# Buck_60W20V_MCU_AuxPSU.net
KiCad netlist of a schematic drawn in Altium Designer
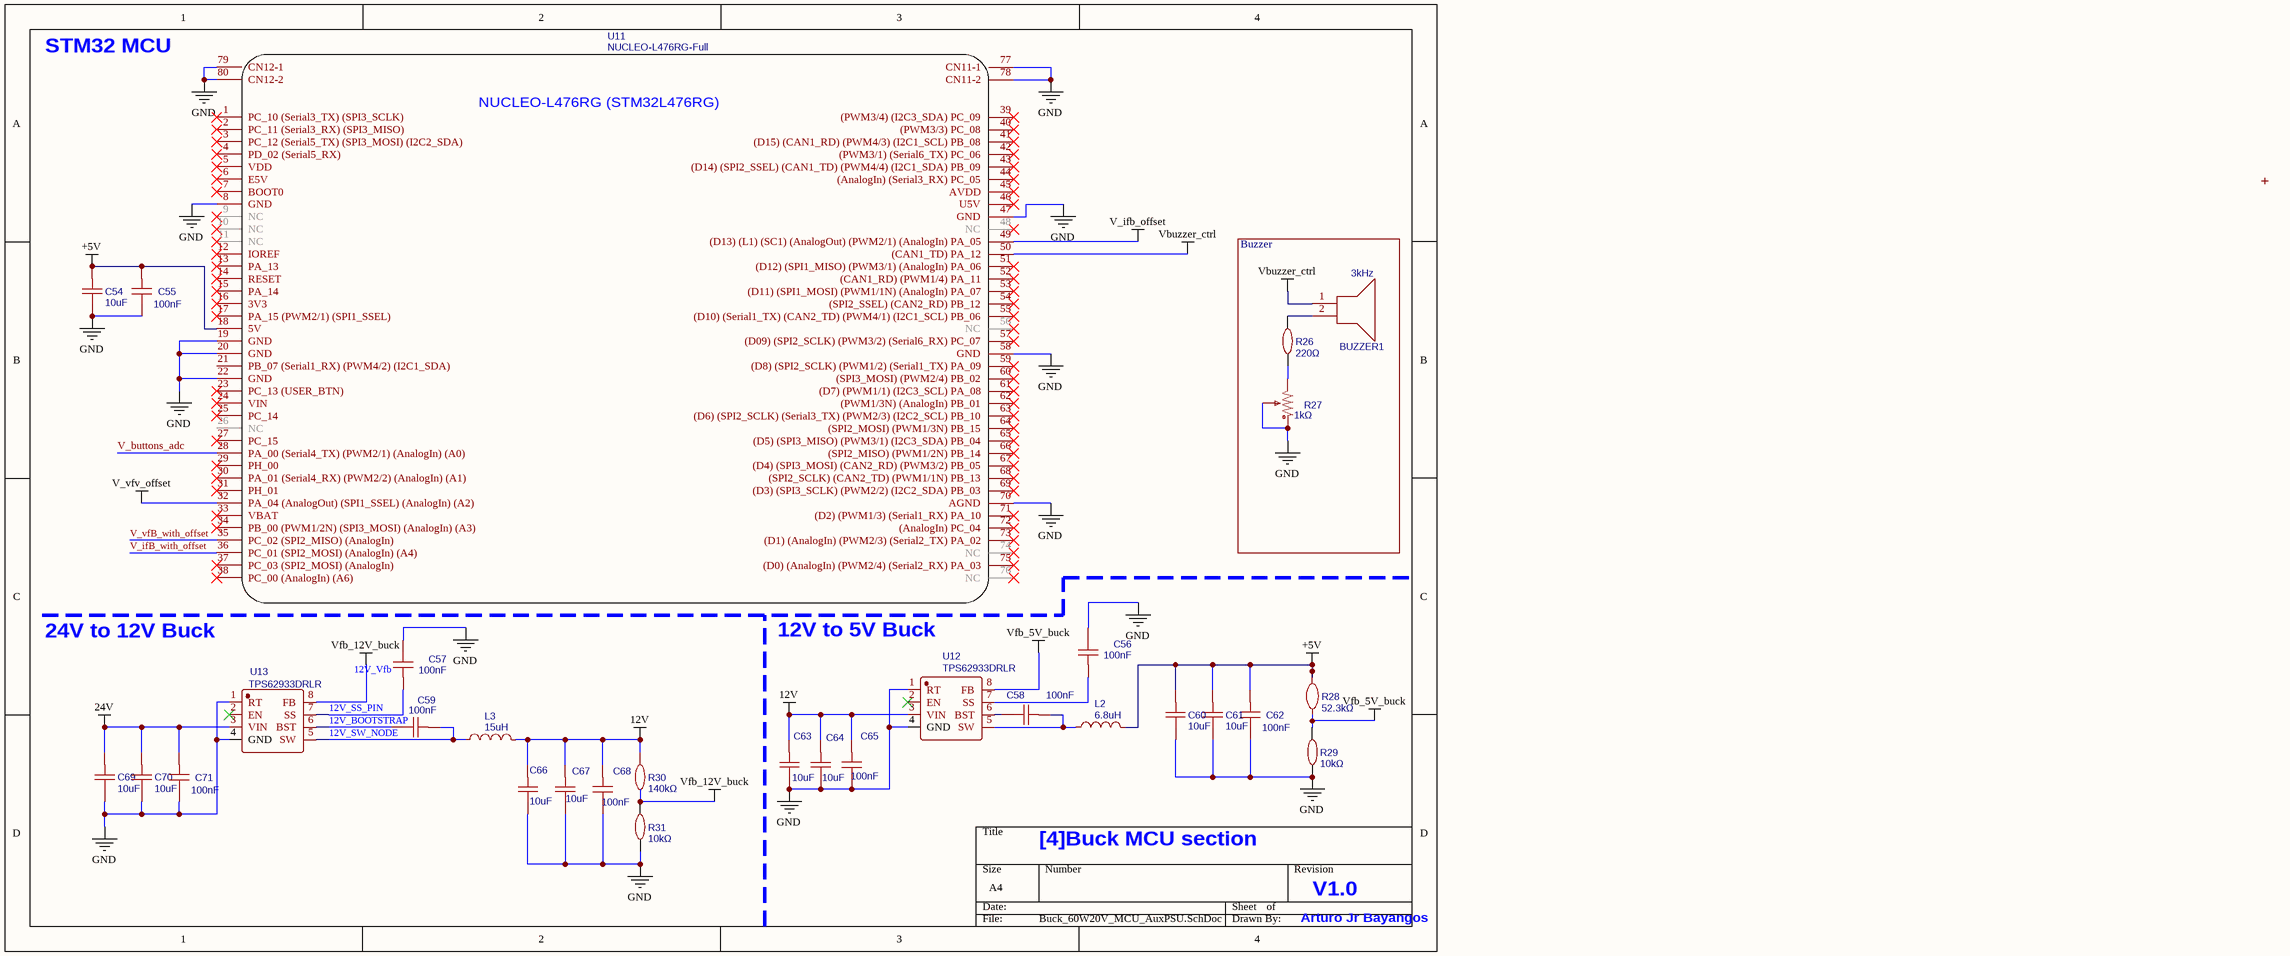
[diagram p0: Buck_60W20V_MCU_AuxPSU.SchDoc]

(export (version "E")
  (design (tool "Eeschema 10.0.6"))
  (components
    (comp (ref "BUZZER1")
      (value "3kHz")
      (footprint "BUZ-TH_BD9.0-P5.00-D0.6-FD")
      (fields
        (field (name "MANUFACTURER") "华能")
        (field (name "MANUFACTURER PART") "HNB09A03")
        (field (name "CONTRIBUTOR") "LCSC")
      )
      (libsource (lib "altium-import") (part "root_0_3kHz_"))
    )
    (comp (ref "C54")
      (value "10uF")
      (footprint "C1210")
      (fields
        (field (name "MANUFACTURER") "TAIYO YUDEN(太诱)")
        (field (name "MANUFACTURER PART") "UMK325AB7106KM-T")
        (field (name "CONTRIBUTOR") "LCSC")
      )
      (libsource (lib "altium-import") (part "root_1_10uF_"))
    )
    (comp (ref "C55")
      (value "100nF")
      (footprint "C0402")
      (fields
        (field (name "MANUFACTURER") "TAIYO YUDEN(太诱)")
        (field (name "MANUFACTURER PART") "UMK105B7104KV-FR")
        (field (name "CONTRIBUTOR") "lcsc")
      )
      (libsource (lib "altium-import") (part "root_1_100nF_"))
    )
    (comp (ref "C56")
      (value "100nF")
      (footprint "C0402")
      (fields
        (field (name "MANUFACTURER") "TAIYO YUDEN(太诱)")
        (field (name "MANUFACTURER PART") "UMK105B7104KV-FR")
        (field (name "CONTRIBUTOR") "lcsc")
      )
      (libsource (lib "altium-import") (part "root_3_100nF_"))
    )
    (comp (ref "C57")
      (value "100nF")
      (footprint "C0402")
      (fields
        (field (name "MANUFACTURER") "TAIYO YUDEN(太诱)")
        (field (name "MANUFACTURER PART") "UMK105B7104KV-FR")
        (field (name "CONTRIBUTOR") "lcsc")
      )
      (libsource (lib "altium-import") (part "root_3_100nF_"))
    )
    (comp (ref "C58")
      (value "100nF")
      (footprint "C0402")
      (fields
        (field (name "MANUFACTURER") "TAIYO YUDEN(太诱)")
        (field (name "MANUFACTURER PART") "UMK105B7104KV-FR")
        (field (name "CONTRIBUTOR") "lcsc")
      )
      (libsource (lib "altium-import") (part "root_0_100nF_"))
    )
    (comp (ref "C59")
      (value "100nF")
      (footprint "C0402")
      (fields
        (field (name "MANUFACTURER") "TAIYO YUDEN(太诱)")
        (field (name "MANUFACTURER PART") "UMK105B7104KV-FR")
        (field (name "CONTRIBUTOR") "lcsc")
      )
      (libsource (lib "altium-import") (part "root_0_100nF_"))
    )
    (comp (ref "C60")
      (value "10uF")
      (footprint "C1210")
      (fields
        (field (name "MANUFACTURER") "TAIYO YUDEN(太诱)")
        (field (name "MANUFACTURER PART") "UMK325AB7106KM-T")
        (field (name "CONTRIBUTOR") "LCSC")
      )
      (libsource (lib "altium-import") (part "root_1_10uF_"))
    )
    (comp (ref "C61")
      (value "10uF")
      (footprint "C1210")
      (fields
        (field (name "MANUFACTURER") "TAIYO YUDEN(太诱)")
        (field (name "MANUFACTURER PART") "UMK325AB7106KM-T")
        (field (name "CONTRIBUTOR") "LCSC")
      )
      (libsource (lib "altium-import") (part "root_1_10uF_"))
    )
    (comp (ref "C62")
      (value "100nF")
      (footprint "C0402")
      (fields
        (field (name "MANUFACTURER") "TAIYO YUDEN(太诱)")
        (field (name "MANUFACTURER PART") "UMK105B7104KV-FR")
        (field (name "CONTRIBUTOR") "lcsc")
      )
      (libsource (lib "altium-import") (part "root_1_100nF_"))
    )
    (comp (ref "C63")
      (value "10uF")
      (footprint "C1210")
      (fields
        (field (name "MANUFACTURER") "TAIYO YUDEN(太诱)")
        (field (name "MANUFACTURER PART") "UMK325AB7106KM-T")
        (field (name "CONTRIBUTOR") "LCSC")
      )
      (libsource (lib "altium-import") (part "root_1_10uF_"))
    )
    (comp (ref "C64")
      (value "10uF")
      (footprint "C1210")
      (fields
        (field (name "MANUFACTURER") "TAIYO YUDEN(太诱)")
        (field (name "MANUFACTURER PART") "UMK325AB7106KM-T")
        (field (name "CONTRIBUTOR") "LCSC")
      )
      (libsource (lib "altium-import") (part "root_1_10uF_"))
    )
    (comp (ref "C65")
      (value "100nF")
      (footprint "C0402")
      (fields
        (field (name "MANUFACTURER") "TAIYO YUDEN(太诱)")
        (field (name "MANUFACTURER PART") "UMK105B7104KV-FR")
        (field (name "CONTRIBUTOR") "lcsc")
      )
      (libsource (lib "altium-import") (part "root_1_100nF_"))
    )
    (comp (ref "C66")
      (value "10uF")
      (footprint "C1210")
      (fields
        (field (name "MANUFACTURER") "TAIYO YUDEN(太诱)")
        (field (name "MANUFACTURER PART") "UMK325AB7106KM-T")
        (field (name "CONTRIBUTOR") "LCSC")
      )
      (libsource (lib "altium-import") (part "root_1_10uF_"))
    )
    (comp (ref "C67")
      (value "10uF")
      (footprint "C1210")
      (fields
        (field (name "MANUFACTURER") "TAIYO YUDEN(太诱)")
        (field (name "MANUFACTURER PART") "UMK325AB7106KM-T")
        (field (name "CONTRIBUTOR") "LCSC")
      )
      (libsource (lib "altium-import") (part "root_1_10uF_"))
    )
    (comp (ref "C68")
      (value "100nF")
      (footprint "C0402")
      (fields
        (field (name "MANUFACTURER") "TAIYO YUDEN(太诱)")
        (field (name "MANUFACTURER PART") "UMK105B7104KV-FR")
        (field (name "CONTRIBUTOR") "lcsc")
      )
      (libsource (lib "altium-import") (part "root_1_100nF_"))
    )
    (comp (ref "C69")
      (value "10uF")
      (footprint "C1210")
      (fields
        (field (name "MANUFACTURER") "TAIYO YUDEN(太诱)")
        (field (name "MANUFACTURER PART") "UMK325AB7106KM-T")
        (field (name "CONTRIBUTOR") "LCSC")
      )
      (libsource (lib "altium-import") (part "root_1_10uF_"))
    )
    (comp (ref "C70")
      (value "10uF")
      (footprint "C1210")
      (fields
        (field (name "MANUFACTURER") "TAIYO YUDEN(太诱)")
        (field (name "MANUFACTURER PART") "UMK325AB7106KM-T")
        (field (name "CONTRIBUTOR") "LCSC")
      )
      (libsource (lib "altium-import") (part "root_1_10uF_"))
    )
    (comp (ref "C71")
      (value "100nF")
      (footprint "C0402")
      (fields
        (field (name "MANUFACTURER") "TAIYO YUDEN(太诱)")
        (field (name "MANUFACTURER PART") "UMK105B7104KV-FR")
        (field (name "CONTRIBUTOR") "lcsc")
      )
      (libsource (lib "altium-import") (part "root_1_100nF_"))
    )
    (comp (ref "L2")
      (value "6.8uH")
      (footprint "IND-SMD_L3.0-W3.0_LQH3NPN")
      (fields
        (field (name "MANUFACTURER") "muRata(村田)")
        (field (name "MANUFACTURER PART") "LQH3NPN6R8MMEL")
        (field (name "CONTRIBUTOR") "lcsc")
      )
      (libsource (lib "altium-import") (part "root_0_6.8uH_"))
    )
    (comp (ref "L3")
      (value "15uH")
      (footprint "IND-SMD_L7.2-W6.9")
      (fields
        (field (name "MANUFACTURER") "TDK")
        (field (name "MANUFACTURER PART") "SPM6545VT-150M-D")
        (field (name "CONTRIBUTOR") "lcsc")
      )
      (libsource (lib "altium-import") (part "root_0_15uH_"))
    )
    (comp (ref "R26")
      (value "220Ω")
      (footprint "R0603")
      (fields (field (name "MANUFACTURER") "RALEC(旺诠)") (field (name "MANUFACTURER PART") "RTT03221JTP"))
      (libsource (lib "altium-import") (part "root_1_220Ω_"))
    )
    (comp (ref "R27")
      (value "1kΩ")
      (footprint "RES-ADJ-TH_3296W")
      (fields
        (field (name "MANUFACTURER") "BOCHEN(博晨)")
        (field (name "MANUFACTURER PART") "3296W-1-102-8mm")
        (field (name "CONTRIBUTOR") "LCSC")
      )
      (libsource (lib "altium-import") (part "root_3_1kΩ_"))
    )
    (comp (ref "R28")
      (value "52.3kΩ")
      (footprint "R0603")
      (fields
        (field (name "MANUFACTURER") "PANASONIC(松下)")
        (field (name "MANUFACTURER PART") "ERA3AEB5232V")
        (field (name "CONTRIBUTOR") "LCSC")
      )
      (libsource (lib "altium-import") (part "root_1_52.3kΩ_"))
    )
    (comp (ref "R29")
      (value "10kΩ")
      (footprint "R0603")
      (fields
        (field (name "MANUFACTURER") "UNI-ROYAL(厚声)")
        (field (name "MANUFACTURER PART") "0603WAF1002T5E")
      )
      (libsource (lib "altium-import") (part "root_1_10kΩ_"))
    )
    (comp (ref "R30")
      (value "140kΩ")
      (footprint "R0603")
      (fields
        (field (name "MANUFACTURER") "Viking(光颉)")
        (field (name "MANUFACTURER PART") "ARG03FTC1403")
        (field (name "CONTRIBUTOR") "LCSC")
      )
      (libsource (lib "altium-import") (part "root_1_140kΩ_"))
    )
    (comp (ref "R31")
      (value "10kΩ")
      (footprint "R0603")
      (fields
        (field (name "MANUFACTURER") "UNI-ROYAL(厚声)")
        (field (name "MANUFACTURER PART") "0603WAF1002T5E")
      )
      (libsource (lib "altium-import") (part "root_1_10kΩ_"))
    )
    (comp (ref "U11")
      (value "NUCLEO-L476RG-Full")
      (footprint "MORPHO HEADER L476RG")
      (fields (field (name "MANUFACTURER PART") "NUCLEO-F446RE") (field (name "CONTRIBUTOR") "ambi bayangos"))
      (libsource (lib "altium-import") (part "root_0_NUCLEO-L476RG-Full_"))
    )
    (comp (ref "U12")
      (value "TPS62933DRLR")
      (footprint "SOT-583-8_L2.1-W1.2-P0.50-LS1.6-BR")
      (fields (field (name "MANUFACTURER") "TI(德州仪器)") (field (name "CONTRIBUTOR") "lcsc"))
      (libsource (lib "altium-import") (part "root_0_TPS62933DRLR_"))
    )
    (comp (ref "U13")
      (value "TPS62933DRLR")
      (footprint "SOT-583-8_L2.1-W1.2-P0.50-LS1.6-BR")
      (fields (field (name "MANUFACTURER") "TI(德州仪器)") (field (name "CONTRIBUTOR") "lcsc"))
      (libsource (lib "altium-import") (part "root_0_TPS62933DRLR_"))
    )
  )
  (nets
    (net (code "1") (name "+5V") (class "Default")
      (node (ref "C54") (pin "2") (pinfunction "2_2") (pintype "passive"))
      (node (ref "C55") (pin "2") (pinfunction "2_2") (pintype "passive"))
      (node (ref "C60") (pin "2") (pinfunction "2_2") (pintype "passive"))
      (node (ref "C61") (pin "2") (pinfunction "2_2") (pintype "passive"))
      (node (ref "C62") (pin "2") (pinfunction "2_2") (pintype "passive"))
      (node (ref "L2") (pin "2") (pinfunction "2_2") (pintype "passive"))
      (node (ref "R28") (pin "2") (pinfunction "2_2") (pintype "passive"))
      (node (ref "U11") (pin "18") (pinfunction "5V_18") (pintype "passive"))
    )
    (net (code "2") (name "/12V_BOOTSTRAP") (class "Default")
      (node (ref "C59") (pin "1") (pinfunction "1_1") (pintype "passive"))
      (node (ref "U13") (pin "6") (pinfunction "BST_6") (pintype "passive"))
    )
    (net (code "3") (name "/12V_SS_PIN") (class "Default")
      (node (ref "C57") (pin "2") (pinfunction "2_2") (pintype "passive"))
      (node (ref "U13") (pin "7") (pinfunction "SS_7") (pintype "passive"))
    )
    (net (code "4") (name "/12V_SW_NODE") (class "Default")
      (node (ref "C59") (pin "2") (pinfunction "2_2") (pintype "passive"))
      (node (ref "L3") (pin "1") (pinfunction "1_1") (pintype "passive"))
      (node (ref "U13") (pin "5") (pinfunction "SW_5") (pintype "passive"))
    )
    (net (code "6") (name "/V_buttons_adc") (class "Default")
      (node (ref "U11") (pin "28") (pinfunction "PA_00_(Serial4_TX)_(PWM2/1)_(AnalogIn)_(A0)_28") (pintype "passive"))
    )
    (net (code "7") (name "/V_ifB_with_offset") (class "Default")
      (node (ref "U11") (pin "36") (pinfunction "PC_01_(SPI2_MOSI)_(AnalogIn)_(A4)_36") (pintype "passive"))
    )
    (net (code "8") (name "/V_vfB_with_offset") (class "Default")
      (node (ref "U11") (pin "35") (pinfunction "PC_02_(SPI2_MISO)_(AnalogIn)_35") (pintype "passive"))
    )
    (net (code "9") (name "12V") (class "Default")
      (node (ref "C63") (pin "2") (pinfunction "2_2") (pintype "passive"))
      (node (ref "C64") (pin "2") (pinfunction "2_2") (pintype "passive"))
      (node (ref "C65") (pin "2") (pinfunction "2_2") (pintype "passive"))
      (node (ref "C66") (pin "2") (pinfunction "2_2") (pintype "passive"))
      (node (ref "C67") (pin "2") (pinfunction "2_2") (pintype "passive"))
      (node (ref "C68") (pin "2") (pinfunction "2_2") (pintype "passive"))
      (node (ref "L3") (pin "2") (pinfunction "2_2") (pintype "passive"))
      (node (ref "R30") (pin "2") (pinfunction "2_2") (pintype "passive"))
      (node (ref "U12") (pin "3") (pinfunction "VIN_3") (pintype "passive"))
    )
    (net (code "10") (name "24V") (class "Default")
      (node (ref "C69") (pin "2") (pinfunction "2_2") (pintype "passive"))
      (node (ref "C70") (pin "2") (pinfunction "2_2") (pintype "passive"))
      (node (ref "C71") (pin "2") (pinfunction "2_2") (pintype "passive"))
      (node (ref "U13") (pin "3") (pinfunction "VIN_3") (pintype "passive"))
    )
    (net (code "11") (name "GND") (class "Default")
      (node (ref "C54") (pin "1") (pinfunction "1_1") (pintype "passive"))
      (node (ref "C55") (pin "1") (pinfunction "1_1") (pintype "passive"))
      (node (ref "C56") (pin "1") (pinfunction "1_1") (pintype "passive"))
      (node (ref "C57") (pin "1") (pinfunction "1_1") (pintype "passive"))
      (node (ref "C60") (pin "1") (pinfunction "1_1") (pintype "passive"))
      (node (ref "C61") (pin "1") (pinfunction "1_1") (pintype "passive"))
      (node (ref "C62") (pin "1") (pinfunction "1_1") (pintype "passive"))
      (node (ref "C63") (pin "1") (pinfunction "1_1") (pintype "passive"))
      (node (ref "C64") (pin "1") (pinfunction "1_1") (pintype "passive"))
      (node (ref "C65") (pin "1") (pinfunction "1_1") (pintype "passive"))
      (node (ref "C66") (pin "1") (pinfunction "1_1") (pintype "passive"))
      (node (ref "C67") (pin "1") (pinfunction "1_1") (pintype "passive"))
      (node (ref "C68") (pin "1") (pinfunction "1_1") (pintype "passive"))
      (node (ref "C69") (pin "1") (pinfunction "1_1") (pintype "passive"))
      (node (ref "C70") (pin "1") (pinfunction "1_1") (pintype "passive"))
      (node (ref "C71") (pin "1") (pinfunction "1_1") (pintype "passive"))
      (node (ref "R27") (pin "1") (pinfunction "1_1") (pintype "passive"))
      (node (ref "R27") (pin "2") (pinfunction "2_2") (pintype "passive"))
      (node (ref "R29") (pin "1") (pinfunction "1_1") (pintype "passive"))
      (node (ref "R31") (pin "1") (pinfunction "1_1") (pintype "passive"))
      (node (ref "U11") (pin "19") (pinfunction "GND_19") (pintype "passive"))
      (node (ref "U11") (pin "20") (pinfunction "GND_20") (pintype "passive"))
      (node (ref "U11") (pin "22") (pinfunction "GND_22") (pintype "passive"))
      (node (ref "U11") (pin "47") (pinfunction "GND_47") (pintype "passive"))
      (node (ref "U11") (pin "58") (pinfunction "GND_58") (pintype "passive"))
      (node (ref "U11") (pin "70") (pinfunction "AGND_70") (pintype "passive"))
      (node (ref "U11") (pin "77") (pinfunction "CN11-1_77") (pintype "passive"))
      (node (ref "U11") (pin "78") (pinfunction "CN11-2_78") (pintype "passive"))
      (node (ref "U11") (pin "79") (pinfunction "CN12-1_79") (pintype "passive"))
      (node (ref "U11") (pin "8") (pinfunction "GND_8") (pintype "passive"))
      (node (ref "U11") (pin "80") (pinfunction "CN12-2_80") (pintype "passive"))
      (node (ref "U12") (pin "1") (pinfunction "RT_1") (pintype "passive"))
      (node (ref "U12") (pin "4") (pinfunction "GND_4") (pintype "passive"))
      (node (ref "U13") (pin "1") (pinfunction "RT_1") (pintype "passive"))
      (node (ref "U13") (pin "4") (pinfunction "GND_4") (pintype "passive"))
    )
    (net (code "12") (name "Net-(BUZZER1--)") (class "Default")
      (node (ref "BUZZER1") (pin "2") (pinfunction "-_2") (pintype "passive"))
      (node (ref "R26") (pin "2") (pinfunction "2_2") (pintype "passive"))
    )
    (net (code "13") (name "Net-(R26-Pad1)") (class "Default")
      (node (ref "R26") (pin "1") (pinfunction "1_1") (pintype "passive"))
      (node (ref "R27") (pin "3") (pinfunction "3_3") (pintype "passive"))
    )
    (net (code "14") (name "Net-(U12-BST)") (class "Default")
      (node (ref "C58") (pin "1") (pinfunction "1_1") (pintype "passive"))
      (node (ref "U12") (pin "6") (pinfunction "BST_6") (pintype "passive"))
    )
    (net (code "15") (name "Net-(U12-SS)") (class "Default")
      (node (ref "C56") (pin "2") (pinfunction "2_2") (pintype "passive"))
      (node (ref "U12") (pin "7") (pinfunction "SS_7") (pintype "passive"))
    )
    (net (code "16") (name "Net-(U12-SW)") (class "Default")
      (node (ref "C58") (pin "2") (pinfunction "2_2") (pintype "passive"))
      (node (ref "L2") (pin "1") (pinfunction "1_1") (pintype "passive"))
      (node (ref "U12") (pin "5") (pinfunction "SW_5") (pintype "passive"))
    )
    (net (code "17") (name "V_ifb_offset") (class "Default")
      (node (ref "U11") (pin "49") (pinfunction "(D13)_(L1)_(SC1)_(AnalogOut)_(PWM2/1)_(AnalogIn)_PA_05_49") (pintype "passive"))
    )
    (net (code "18") (name "V_vfv_offset") (class "Default")
      (node (ref "U11") (pin "32") (pinfunction "PA_04_(AnalogOut)_(SPI1_SSEL)_(AnalogIn)_(A2)_32") (pintype "passive"))
    )
    (net (code "19") (name "Vbuzzer_ctrl") (class "Default")
      (node (ref "BUZZER1") (pin "1") (pinfunction "+_1") (pintype "passive"))
      (node (ref "U11") (pin "50") (pinfunction "(CAN1_TD)_PA_12_50") (pintype "passive"))
    )
    (net (code "20") (name "Vfb_5V_buck") (class "Default")
      (node (ref "R28") (pin "1") (pinfunction "1_1") (pintype "passive"))
      (node (ref "R29") (pin "2") (pinfunction "2_2") (pintype "passive"))
      (node (ref "U12") (pin "8") (pinfunction "FB_8") (pintype "passive"))
    )
    (net (code "21") (name "Vfb_12V_buck") (class "Default")
      (node (ref "R30") (pin "1") (pinfunction "1_1") (pintype "passive"))
      (node (ref "R31") (pin "2") (pinfunction "2_2") (pintype "passive"))
      (node (ref "U13") (pin "8") (pinfunction "FB_8") (pintype "passive"))
    )
    (net (code "22") (name "unconnected-(U11-(AnalogIn)_(Serial3_RX)_PC_05-Pad44)") (class "Default")
      (node (ref "U11") (pin "44") (pinfunction "(AnalogIn)_(Serial3_RX)_PC_05_44") (pintype "passive+no_connect"))
    )
    (net (code "23") (name "unconnected-(U11-(AnalogIn)_PC_04-Pad72)") (class "Default")
      (node (ref "U11") (pin "72") (pinfunction "(AnalogIn)_PC_04_72") (pintype "passive+no_connect"))
    )
    (net (code "24") (name "unconnected-(U11-(CAN1_RD)_(PWM1{slash}4)_PA_11-Pad52)") (class "Default")
      (node (ref "U11") (pin "52") (pinfunction "(CAN1_RD)_(PWM1/4)_PA_11_52") (pintype "passive+no_connect"))
    )
    (net (code "25") (name "unconnected-(U11-(D0)_(AnalogIn)_(PWM2{slash}4)_(Serial2_RX)_PA_03-Pad75)") (class "Default")
      (node (ref "U11") (pin "75") (pinfunction "(D0)_(AnalogIn)_(PWM2/4)_(Serial2_RX)_PA_03_75") (pintype "passive+no_connect"))
    )
    (net (code "26") (name "unconnected-(U11-(D1)_(AnalogIn)_(PWM2{slash}3)_(Serial2_TX)_PA_02-Pad73)") (class "Default")
      (node (ref "U11") (pin "73") (pinfunction "(D1)_(AnalogIn)_(PWM2/3)_(Serial2_TX)_PA_02_73") (pintype "passive+no_connect"))
    )
    (net (code "27") (name "unconnected-(U11-(D2)_(PWM1{slash}3)_(Serial1_RX)_PA_10-Pad71)") (class "Default")
      (node (ref "U11") (pin "71") (pinfunction "(D2)_(PWM1/3)_(Serial1_RX)_PA_10_71") (pintype "passive+no_connect"))
    )
    (net (code "28") (name "unconnected-(U11-(D3)_(SPI3_SCLK)_(PWM2{slash}2)_(I2C2_SDA)_PB_03-Pad69)") (class "Default")
      (node (ref "U11") (pin "69") (pinfunction "(D3)_(SPI3_SCLK)_(PWM2/2)_(I2C2_SDA)_PB_03_69") (pintype "passive+no_connect"))
    )
    (net (code "29") (name "unconnected-(U11-(D4)_(SPI3_MOSI)_(CAN2_RD)_(PWM3{slash}2)_PB_05-Pad67)") (class "Default")
      (node (ref "U11") (pin "67") (pinfunction "(D4)_(SPI3_MOSI)_(CAN2_RD)_(PWM3/2)_PB_05_67") (pintype "passive+no_connect"))
    )
    (net (code "30") (name "unconnected-(U11-(D5)_(SPI3_MISO)_(PWM3{slash}1)_(I2C3_SDA)_PB_04-Pad65)") (class "Default")
      (node (ref "U11") (pin "65") (pinfunction "(D5)_(SPI3_MISO)_(PWM3/1)_(I2C3_SDA)_PB_04_65") (pintype "passive+no_connect"))
    )
    (net (code "31") (name "unconnected-(U11-(D6)_(SPI2_SCLK)_(Serial3_TX)_(PWM2{slash}3)_(I2C2_SCL)_PB_10-Pad63)") (class "Default")
      (node (ref "U11") (pin "63") (pinfunction "(D6)_(SPI2_SCLK)_(Serial3_TX)_(PWM2/3)_(I2C2_SCL)_PB_10_63") (pintype "passive+no_connect"))
    )
    (net (code "32") (name "unconnected-(U11-(D7)_(PWM1{slash}1)_(I2C3_SCL)_PA_08-Pad61)") (class "Default")
      (node (ref "U11") (pin "61") (pinfunction "(D7)_(PWM1/1)_(I2C3_SCL)_PA_08_61") (pintype "passive+no_connect"))
    )
    (net (code "33") (name "unconnected-(U11-(D8)_(SPI2_SCLK)_(PWM1{slash}2)_(Serial1_TX)_PA_09-Pad59)") (class "Default")
      (node (ref "U11") (pin "59") (pinfunction "(D8)_(SPI2_SCLK)_(PWM1/2)_(Serial1_TX)_PA_09_59") (pintype "passive+no_connect"))
    )
    (net (code "34") (name "unconnected-(U11-(D09)_(SPI2_SCLK)_(PWM3{slash}2)_(Serial6_RX)_PC_07-Pad57)") (class "Default")
      (node (ref "U11") (pin "57") (pinfunction "(D09)_(SPI2_SCLK)_(PWM3/2)_(Serial6_RX)_PC_07_57") (pintype "passive+no_connect"))
    )
    (net (code "35") (name "unconnected-(U11-(D10)_(Serial1_TX)_(CAN2_TD)_(PWM4{slash}1)_(I2C1_SCL)_PB_06-Pad55)") (class "Default")
      (node (ref "U11") (pin "55") (pinfunction "(D10)_(Serial1_TX)_(CAN2_TD)_(PWM4/1)_(I2C1_SCL)_PB_06_55") (pintype "passive+no_connect"))
    )
    (net (code "36") (name "unconnected-(U11-(D11)_(SPI1_MOSI)_(PWM1{slash}1N)_(AnalogIn)_PA_07-Pad53)") (class "Default")
      (node (ref "U11") (pin "53") (pinfunction "(D11)_(SPI1_MOSI)_(PWM1/1N)_(AnalogIn)_PA_07_53") (pintype "passive+no_connect"))
    )
    (net (code "37") (name "unconnected-(U11-(D12)_(SPI1_MISO)_(PWM3{slash}1)_(AnalogIn)_PA_06-Pad51)") (class "Default")
      (node (ref "U11") (pin "51") (pinfunction "(D12)_(SPI1_MISO)_(PWM3/1)_(AnalogIn)_PA_06_51") (pintype "passive+no_connect"))
    )
    (net (code "38") (name "unconnected-(U11-(D14)_(SPI2_SSEL)_(CAN1_TD)_(PWM4{slash}4)_(I2C1_SDA)_PB_09-Pad43)") (class "Default")
      (node (ref "U11") (pin "43") (pinfunction "(D14)_(SPI2_SSEL)_(CAN1_TD)_(PWM4/4)_(I2C1_SDA)_PB_09_43") (pintype "passive+no_connect"))
    )
    (net (code "39") (name "unconnected-(U11-(D15)_(CAN1_RD)_(PWM4{slash}3)_(I2C1_SCL)_PB_08-Pad41)") (class "Default")
      (node (ref "U11") (pin "41") (pinfunction "(D15)_(CAN1_RD)_(PWM4/3)_(I2C1_SCL)_PB_08_41") (pintype "passive+no_connect"))
    )
    (net (code "40") (name "unconnected-(U11-(PWM1{slash}3N)_(AnalogIn)_PB_01-Pad62)") (class "Default")
      (node (ref "U11") (pin "62") (pinfunction "(PWM1/3N)_(AnalogIn)_PB_01_62") (pintype "passive+no_connect"))
    )
    (net (code "41") (name "unconnected-(U11-(PWM3{slash}1)_(Serial6_TX)_PC_06-Pad42)") (class "Default")
      (node (ref "U11") (pin "42") (pinfunction "(PWM3/1)_(Serial6_TX)_PC_06_42") (pintype "passive+no_connect"))
    )
    (net (code "42") (name "unconnected-(U11-(PWM3{slash}3)_PC_08-Pad40)") (class "Default")
      (node (ref "U11") (pin "40") (pinfunction "(PWM3/3)_PC_08_40") (pintype "passive+no_connect"))
    )
    (net (code "43") (name "unconnected-(U11-(PWM3{slash}4)_(I2C3_SDA)_PC_09-Pad39)") (class "Default")
      (node (ref "U11") (pin "39") (pinfunction "(PWM3/4)_(I2C3_SDA)_PC_09_39") (pintype "passive+no_connect"))
    )
    (net (code "44") (name "unconnected-(U11-(SPI2_MISO)_(PWM1{slash}2N)_PB_14-Pad66)") (class "Default")
      (node (ref "U11") (pin "66") (pinfunction "(SPI2_MISO)_(PWM1/2N)_PB_14_66") (pintype "passive+no_connect"))
    )
    (net (code "45") (name "unconnected-(U11-(SPI2_MOSI)_(PWM1{slash}3N)_PB_15-Pad64)") (class "Default")
      (node (ref "U11") (pin "64") (pinfunction "(SPI2_MOSI)_(PWM1/3N)_PB_15_64") (pintype "passive+no_connect"))
    )
    (net (code "46") (name "unconnected-(U11-(SPI2_SCLK)_(CAN2_TD)_(PWM1{slash}1N)_PB_13-Pad68)") (class "Default")
      (node (ref "U11") (pin "68") (pinfunction "(SPI2_SCLK)_(CAN2_TD)_(PWM1/1N)_PB_13_68") (pintype "passive+no_connect"))
    )
    (net (code "47") (name "unconnected-(U11-(SPI2_SSEL)_(CAN2_RD)_PB_12-Pad54)") (class "Default")
      (node (ref "U11") (pin "54") (pinfunction "(SPI2_SSEL)_(CAN2_RD)_PB_12_54") (pintype "passive+no_connect"))
    )
    (net (code "48") (name "unconnected-(U11-(SPI3_MOSI)_(PWM2{slash}4)_PB_02-Pad60)") (class "Default")
      (node (ref "U11") (pin "60") (pinfunction "(SPI3_MOSI)_(PWM2/4)_PB_02_60") (pintype "passive+no_connect"))
    )
    (net (code "49") (name "unconnected-(U11-3V3-Pad16)") (class "Default")
      (node (ref "U11") (pin "16") (pinfunction "3V3_16") (pintype "passive+no_connect"))
    )
    (net (code "50") (name "unconnected-(U11-AVDD-Pad45)") (class "Default")
      (node (ref "U11") (pin "45") (pinfunction "AVDD_45") (pintype "passive+no_connect"))
    )
    (net (code "51") (name "unconnected-(U11-BOOT0-Pad7)") (class "Default")
      (node (ref "U11") (pin "7") (pinfunction "BOOT0_7") (pintype "passive+no_connect"))
    )
    (net (code "52") (name "unconnected-(U11-E5V-Pad6)") (class "Default")
      (node (ref "U11") (pin "6") (pinfunction "E5V_6") (pintype "passive+no_connect"))
    )
    (net (code "53") (name "unconnected-(U11-IOREF-Pad12)") (class "Default")
      (node (ref "U11") (pin "12") (pinfunction "IOREF_12") (pintype "passive+no_connect"))
    )
    (net (code "54") (name "unconnected-(U11-NC-Pad9)") (class "Default")
      (node (ref "U11") (pin "9") (pinfunction "NC_9") (pintype "passive+no_connect"))
    )
    (net (code "55") (name "unconnected-(U11-NC-Pad10)") (class "Default")
      (node (ref "U11") (pin "10") (pinfunction "NC_10") (pintype "passive+no_connect"))
    )
    (net (code "56") (name "unconnected-(U11-NC-Pad11)") (class "Default")
      (node (ref "U11") (pin "11") (pinfunction "NC_11") (pintype "passive+no_connect"))
    )
    (net (code "57") (name "unconnected-(U11-NC-Pad26)") (class "Default")
      (node (ref "U11") (pin "26") (pinfunction "NC_26") (pintype "passive"))
    )
    (net (code "58") (name "unconnected-(U11-NC-Pad48)") (class "Default")
      (node (ref "U11") (pin "48") (pinfunction "NC_48") (pintype "passive+no_connect"))
    )
    (net (code "59") (name "unconnected-(U11-NC-Pad56)") (class "Default")
      (node (ref "U11") (pin "56") (pinfunction "NC_56") (pintype "passive+no_connect"))
    )
    (net (code "60") (name "unconnected-(U11-NC-Pad74)") (class "Default")
      (node (ref "U11") (pin "74") (pinfunction "NC_74") (pintype "passive+no_connect"))
    )
    (net (code "61") (name "unconnected-(U11-NC-Pad76)") (class "Default")
      (node (ref "U11") (pin "76") (pinfunction "NC_76") (pintype "passive+no_connect"))
    )
    (net (code "62") (name "unconnected-(U11-PA_01_(Serial4_RX)_(PWM2{slash}2)_(AnalogIn)_(A1)-Pad30)") (class "Default")
      (node (ref "U11") (pin "30") (pinfunction "PA_01_(Serial4_RX)_(PWM2/2)_(AnalogIn)_(A1)_30") (pintype "passive+no_connect"))
    )
    (net (code "63") (name "unconnected-(U11-PA_13-Pad13)") (class "Default")
      (node (ref "U11") (pin "13") (pinfunction "PA_13_13") (pintype "passive+no_connect"))
    )
    (net (code "64") (name "unconnected-(U11-PA_14-Pad15)") (class "Default")
      (node (ref "U11") (pin "15") (pinfunction "PA_14_15") (pintype "passive+no_connect"))
    )
    (net (code "65") (name "unconnected-(U11-PA_15_(PWM2{slash}1)_(SPI1_SSEL)-Pad17)") (class "Default")
      (node (ref "U11") (pin "17") (pinfunction "PA_15_(PWM2/1)_(SPI1_SSEL)_17") (pintype "passive+no_connect"))
    )
    (net (code "66") (name "unconnected-(U11-PB_00_(PWM1{slash}2N)_(SPI3_MOSI)_(AnalogIn)_(A3)-Pad34)") (class "Default")
      (node (ref "U11") (pin "34") (pinfunction "PB_00_(PWM1/2N)_(SPI3_MOSI)_(AnalogIn)_(A3)_34") (pintype "passive+no_connect"))
    )
    (net (code "67") (name "unconnected-(U11-PB_07_(Serial1_RX)_(PWM4{slash}2)_(I2C1_SDA)-Pad21)") (class "Default")
      (node (ref "U11") (pin "21") (pinfunction "PB_07_(Serial1_RX)_(PWM4/2)_(I2C1_SDA)_21") (pintype "passive"))
    )
    (net (code "68") (name "unconnected-(U11-PC_00_(AnalogIn)_(A6)-Pad38)") (class "Default")
      (node (ref "U11") (pin "38") (pinfunction "PC_00_(AnalogIn)_(A6)_38") (pintype "passive+no_connect"))
    )
    (net (code "69") (name "unconnected-(U11-PC_03_(SPI2_MOSI)_(AnalogIn)-Pad37)") (class "Default")
      (node (ref "U11") (pin "37") (pinfunction "PC_03_(SPI2_MOSI)_(AnalogIn)_37") (pintype "passive+no_connect"))
    )
    (net (code "70") (name "unconnected-(U11-PC_10_(Serial3_TX)_(SPI3_SCLK)-Pad1)") (class "Default")
      (node (ref "U11") (pin "1") (pinfunction "PC_10_(Serial3_TX)_(SPI3_SCLK)_1") (pintype "passive+no_connect"))
    )
    (net (code "71") (name "unconnected-(U11-PC_11_(Serial3_RX)_(SPI3_MISO)-Pad2)") (class "Default")
      (node (ref "U11") (pin "2") (pinfunction "PC_11_(Serial3_RX)_(SPI3_MISO)_2") (pintype "passive+no_connect"))
    )
    (net (code "72") (name "unconnected-(U11-PC_12_(Serial5_TX)_(SPI3_MOSI)_(I2C2_SDA)-Pad3)") (class "Default")
      (node (ref "U11") (pin "3") (pinfunction "PC_12_(Serial5_TX)_(SPI3_MOSI)_(I2C2_SDA)_3") (pintype "passive+no_connect"))
    )
    (net (code "73") (name "unconnected-(U11-PC_13_(USER_BTN)-Pad23)") (class "Default")
      (node (ref "U11") (pin "23") (pinfunction "PC_13_(USER_BTN)_23") (pintype "passive+no_connect"))
    )
    (net (code "74") (name "unconnected-(U11-PC_14-Pad25)") (class "Default")
      (node (ref "U11") (pin "25") (pinfunction "PC_14_25") (pintype "passive+no_connect"))
    )
    (net (code "75") (name "unconnected-(U11-PC_15-Pad27)") (class "Default")
      (node (ref "U11") (pin "27") (pinfunction "PC_15_27") (pintype "passive+no_connect"))
    )
    (net (code "76") (name "unconnected-(U11-PD_02_(Serial5_RX)-Pad4)") (class "Default")
      (node (ref "U11") (pin "4") (pinfunction "PD_02_(Serial5_RX)_4") (pintype "passive+no_connect"))
    )
    (net (code "77") (name "unconnected-(U11-PH_00-Pad29)") (class "Default")
      (node (ref "U11") (pin "29") (pinfunction "PH_00_29") (pintype "passive+no_connect"))
    )
    (net (code "78") (name "unconnected-(U11-PH_01-Pad31)") (class "Default")
      (node (ref "U11") (pin "31") (pinfunction "PH_01_31") (pintype "passive+no_connect"))
    )
    (net (code "79") (name "unconnected-(U11-RESET-Pad14)") (class "Default")
      (node (ref "U11") (pin "14") (pinfunction "RESET_14") (pintype "passive+no_connect"))
    )
    (net (code "80") (name "unconnected-(U11-U5V-Pad46)") (class "Default")
      (node (ref "U11") (pin "46") (pinfunction "U5V_46") (pintype "passive+no_connect"))
    )
    (net (code "81") (name "unconnected-(U11-VBAT-Pad33)") (class "Default")
      (node (ref "U11") (pin "33") (pinfunction "VBAT_33") (pintype "passive+no_connect"))
    )
    (net (code "82") (name "unconnected-(U11-VDD-Pad5)") (class "Default")
      (node (ref "U11") (pin "5") (pinfunction "VDD_5") (pintype "passive+no_connect"))
    )
    (net (code "83") (name "unconnected-(U11-VIN-Pad24)") (class "Default")
      (node (ref "U11") (pin "24") (pinfunction "VIN_24") (pintype "passive+no_connect"))
    )
    (net (code "84") (name "unconnected-(U12-EN-Pad2)") (class "Default")
      (node (ref "U12") (pin "2") (pinfunction "EN_2") (pintype "passive+no_connect"))
    )
    (net (code "85") (name "unconnected-(U13-EN-Pad2)") (class "Default")
      (node (ref "U13") (pin "2") (pinfunction "EN_2") (pintype "passive+no_connect"))
    )
  )
)
